# design.net
KiCad netlist of a schematic drawn in Altium Designer
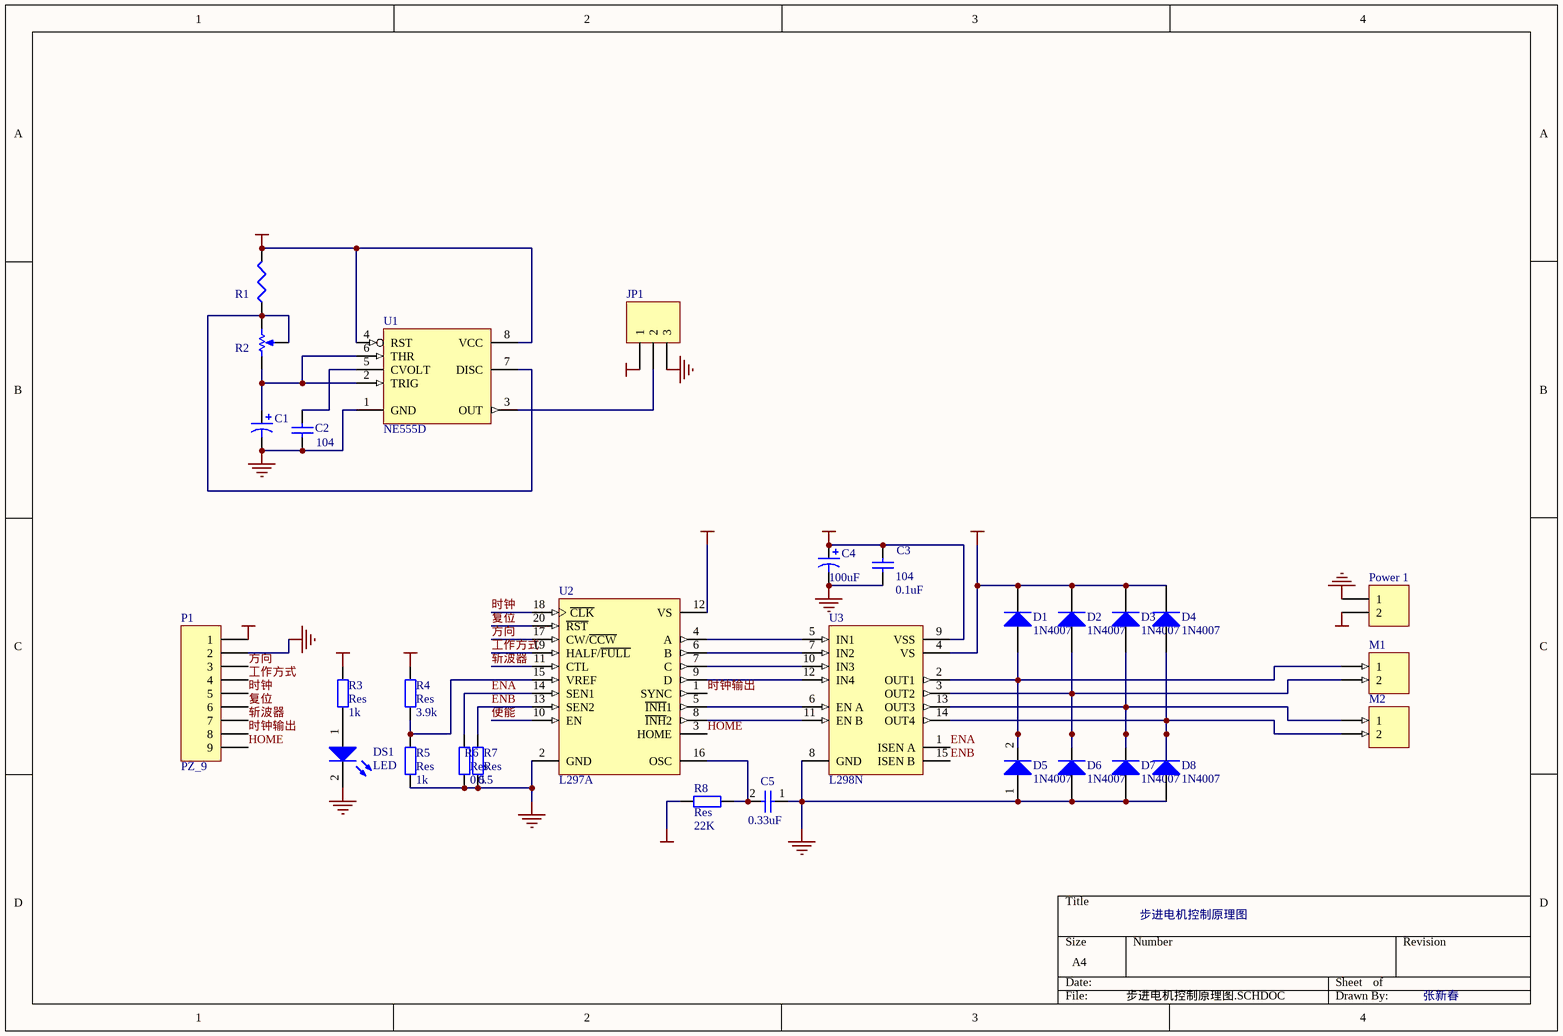
[diagram p0: 步进电机控制原理图.SCHDOC]

(export (version "E")
  (design (tool "Eeschema 10.0.6"))
  (components
    (comp (ref "C1")
      (value "~")
      (footprint "C-DJ-4")
      (description "Polarized Capacitor (Radial)")
      (fields (field (name "PUBLISHER") "Altium Limited"))
      (libsource (lib "Miscellaneous Devices") (part "Cap Pol1"))
    )
    (comp (ref "C2")
      (value "104")
      (footprint "C1608-0603")
      (description "Capacitor (Semiconductor SIM Model)")
      (fields (field (name "PUBLISHER") "Altium Limited"))
      (libsource (lib "Miscellaneous Devices") (part "Cap Semi"))
    )
    (comp (ref "C3")
      (value "104")
      (footprint "CPDR")
      (description "Capacitor")
      (fields (field (name "ALTIUM_VALUE") "0.1uF") (field (name "PUBLISHER") "Altium Limited"))
      (libsource (lib "Miscellaneous Devices") (part "Cap"))
    )
    (comp (ref "C4")
      (value "100uF")
      (footprint "C-DJ-6")
      (description "Polarized Capacitor (Surface Mount)")
      (fields (field (name "PUBLISHER") "Altium Limited"))
      (libsource (lib "Miscellaneous Devices") (part "Cap Pol3"))
    )
    (comp (ref "C5")
      (value "0.33uF")
      (footprint "C-DJ-4")
      (description "Capacitor")
      (fields (field (name "PUBLISHER") "Altium Limited"))
      (libsource (lib "") (part "Cap_1"))
    )
    (comp (ref "D1")
      (value "1N4007")
      (footprint "D-ZL-10")
      (description "1 Amp General Purpose Rectifier")
      (fields (field (name "PUBLISHER") "Altium Limited"))
      (libsource (lib "Miscellaneous Devices") (part "Diode 1N4007"))
    )
    (comp (ref "D2")
      (value "1N4007")
      (footprint "D-ZL-10")
      (description "1 Amp General Purpose Rectifier")
      (fields (field (name "PUBLISHER") "Altium Limited"))
      (libsource (lib "Miscellaneous Devices") (part "Diode 1N4007"))
    )
    (comp (ref "D3")
      (value "1N4007")
      (footprint "D-ZL-10")
      (description "1 Amp General Purpose Rectifier")
      (fields (field (name "PUBLISHER") "Altium Limited"))
      (libsource (lib "Miscellaneous Devices") (part "Diode 1N4007"))
    )
    (comp (ref "D4")
      (value "1N4007")
      (footprint "D-ZL-10")
      (description "1 Amp General Purpose Rectifier")
      (fields (field (name "PUBLISHER") "Altium Limited"))
      (libsource (lib "Miscellaneous Devices") (part "Diode 1N4007"))
    )
    (comp (ref "D5")
      (value "1N4007")
      (footprint "D-ZL-10")
      (description "1 Amp General Purpose Rectifier")
      (fields (field (name "PUBLISHER") "Altium Limited"))
      (libsource (lib "") (part "Diode 1N4007_1"))
    )
    (comp (ref "D6")
      (value "1N4007")
      (footprint "D-ZL-10")
      (description "1 Amp General Purpose Rectifier")
      (fields (field (name "PUBLISHER") "Altium Limited"))
      (libsource (lib "Miscellaneous Devices") (part "Diode 1N4007"))
    )
    (comp (ref "D7")
      (value "1N4007")
      (footprint "D-ZL-10")
      (description "1 Amp General Purpose Rectifier")
      (fields (field (name "PUBLISHER") "Altium Limited"))
      (libsource (lib "Miscellaneous Devices") (part "Diode 1N4007"))
    )
    (comp (ref "D8")
      (value "1N4007")
      (footprint "D-ZL-10")
      (description "1 Amp General Purpose Rectifier")
      (fields (field (name "PUBLISHER") "Altium Limited"))
      (libsource (lib "Miscellaneous Devices") (part "Diode 1N4007"))
    )
    (comp (ref "DS1")
      (value "LED")
      (footprint "CPDR")
      (description "发光二极管")
      (fields (field (name "PUBLISHER") "Altium Limited"))
      (libsource (lib "zxcourhc") (part "LED"))
    )
    (comp (ref "JP1")
      (value "~")
      (footprint "HDR1X3")
      (description "Header, 3-Pin")
      (fields (field (name "PUBLISHER") "Altium Limited"))
      (libsource (lib "Miscellaneous Connectors") (part "Header 3"))
    )
    (comp (ref "M1")
      (value "~")
      (footprint "JK128")
      (description "Header, 2-Pin")
      (fields (field (name "PUBLISHER") "Altium Limited"))
      (libsource (lib "Miscellaneous Connectors") (part "MHDR1X2"))
    )
    (comp (ref "M2")
      (value "~")
      (footprint "JK128")
      (description "Header, 2-Pin")
      (fields (field (name "PUBLISHER") "Altium Limited"))
      (libsource (lib "Miscellaneous Connectors") (part "MHDR1X2"))
    )
    (comp (ref "P1")
      (value "PZ_9")
      (footprint "HDR-9")
      (description "排针——9")
      (fields (field (name "PUBLISHER") "Altium Limited"))
      (libsource (lib "zxcourhc") (part "PZ_9"))
    )
    (comp (ref "Power 1")
      (value "~")
      (footprint "JK128")
      (description "Header, 2-Pin")
      (fields (field (name "PUBLISHER") "Altium Limited"))
      (libsource (lib "Miscellaneous Connectors") (part "MHDR1X2"))
    )
    (comp (ref "R1")
      (value "~")
      (footprint "C1608-0603")
      (description "Resistor")
      (fields (field (name "PUBLISHER") "Altium Limited"))
      (libsource (lib "Miscellaneous Devices") (part "Res3"))
    )
    (comp (ref "R2")
      (value "~")
      (footprint "SIP3-D")
      (description "Potentiometer")
      (fields (field (name "PUBLISHER") "Altium Limited"))
      (libsource (lib "Miscellaneous Devices") (part "RPot"))
    )
    (comp (ref "R3")
      (value "Res")
      (footprint "zxcourhc:CPDR")
      (description "电阻")
      (fields (field (name "ALTIUM_VALUE") "1k") (field (name "PUBLISHER") "Altium Limited"))
      (libsource (lib "zxcourhc") (part "Res"))
    )
    (comp (ref "R4")
      (value "Res")
      (footprint "zxcourhc:CPDR")
      (description "电阻")
      (fields (field (name "ALTIUM_VALUE") "3.9k") (field (name "PUBLISHER") "Altium Limited"))
      (libsource (lib "zxcourhc") (part "Res"))
    )
    (comp (ref "R5")
      (value "Res")
      (footprint "CPDR")
      (description "电阻")
      (fields (field (name "ALTIUM_VALUE") "1k") (field (name "PUBLISHER") "Altium Limited"))
      (libsource (lib "zxcourhc") (part "Res"))
    )
    (comp (ref "R6")
      (value "Res")
      (footprint "ZCDZl")
      (description "电阻")
      (fields (field (name "ALTIUM_VALUE") "0.5") (field (name "PUBLISHER") "Altium Limited"))
      (libsource (lib "zxcourhc") (part "Res"))
    )
    (comp (ref "R7")
      (value "Res")
      (footprint "ZCDZl")
      (description "电阻")
      (fields (field (name "ALTIUM_VALUE") "0.5") (field (name "PUBLISHER") "Altium Limited"))
      (libsource (lib "zxcourhc") (part "Res"))
    )
    (comp (ref "R8")
      (value "Res")
      (footprint "CPDR")
      (description "电阻")
      (fields (field (name "ALTIUM_VALUE") "22K") (field (name "PUBLISHER") "Altium Limited"))
      (libsource (lib "") (part "Res_1"))
    )
    (comp (ref "U1")
      (value "NE555D")
      (footprint "CDFP-8")
      (description "Precision Timer")
      (fields (field (name "MANUFACTURER") "Texas Instruments") (field (name "PUBLISHER") "Altium Limited"))
      (libsource (lib "TI Analog Timer Circuit") (part "NE555D"))
    )
    (comp (ref "U2")
      (value "L297A")
      (footprint "DIP20")
      (description "Stepper Motor Controller")
      (fields (field (name "PUBLISHER") "Altium Limited"))
      (libsource (lib "ST Interface Stepper Motor Controller") (part "L297A"))
    )
    (comp (ref "U3")
      (value "L298N")
      (footprint "zxcourhc:L298N")
      (description "Dual Full Bridge Driver")
      (fields (field (name "PUBLISHER") "Altium Limited"))
      (libsource (lib "ST Interface DC Motor Controller") (part "L298N"))
    )
  )
  (nets
    (net (code "1") (name "+5V") (class "Default")
      (node (ref "C3") (pin "2") (pinfunction "2_2") (pintype "passive"))
      (node (ref "C4") (pin "1") (pinfunction "1_1") (pintype "passive"))
      (node (ref "P1") (pin "1") (pinfunction "1_1") (pintype "passive"))
      (node (ref "R3") (pin "1") (pinfunction "1_1") (pintype "passive"))
      (node (ref "R4") (pin "1") (pinfunction "1_1") (pintype "passive"))
      (node (ref "R8") (pin "2") (pinfunction "2_2") (pintype "passive"))
      (node (ref "U2") (pin "12") (pinfunction "VS_12") (pintype "power_in"))
      (node (ref "U3") (pin "9") (pinfunction "VSS_9") (pintype "power_in"))
    )
    (net (code "2") (name "/ENA") (class "Default")
      (node (ref "R6") (pin "1") (pinfunction "1_1") (pintype "passive"))
      (node (ref "U2") (pin "14") (pinfunction "SEN1_14") (pintype "input"))
      (node (ref "U3") (pin "1") (pinfunction "ISEN_A_1") (pintype "passive"))
    )
    (net (code "3") (name "/ENB") (class "Default")
      (node (ref "R7") (pin "1") (pinfunction "1_1") (pintype "passive"))
      (node (ref "U2") (pin "13") (pinfunction "SEN2_13") (pintype "input"))
      (node (ref "U3") (pin "15") (pinfunction "ISEN_B_15") (pintype "passive"))
    )
    (net (code "4") (name "/HOME") (class "Default")
      (node (ref "P1") (pin "9") (pinfunction "9_9") (pintype "passive"))
      (node (ref "U2") (pin "3") (pinfunction "HOME_3") (pintype "open_collector"))
    )
    (net (code "5") (name "/使能") (class "Default")
      (node (ref "U2") (pin "10") (pinfunction "EN_10") (pintype "input"))
    )
    (net (code "6") (name "/复位") (class "Default")
      (node (ref "P1") (pin "6") (pinfunction "6_6") (pintype "passive"))
      (node (ref "U2") (pin "20") (pinfunction "~{RST}_20") (pintype "input"))
    )
    (net (code "7") (name "/工作方式") (class "Default")
      (node (ref "P1") (pin "4") (pinfunction "4_4") (pintype "passive"))
      (node (ref "U2") (pin "19") (pinfunction "HALF/~{FULL}_19") (pintype "input"))
    )
    (net (code "8") (name "/斩波器") (class "Default")
      (node (ref "P1") (pin "7") (pinfunction "7_7") (pintype "passive"))
      (node (ref "U2") (pin "11") (pinfunction "CTL_11") (pintype "input"))
    )
    (net (code "9") (name "/方向") (class "Default")
      (node (ref "P1") (pin "3") (pinfunction "3_3") (pintype "passive"))
      (node (ref "U2") (pin "17") (pinfunction "CW/~{CCW}_17") (pintype "input"))
    )
    (net (code "10") (name "/时钟") (class "Default")
      (node (ref "P1") (pin "5") (pinfunction "5_5") (pintype "passive"))
      (node (ref "U2") (pin "18") (pinfunction "~{CLK}_18") (pintype "input"))
    )
    (net (code "11") (name "/时钟输出") (class "Default")
      (node (ref "P1") (pin "8") (pinfunction "8_8") (pintype "passive"))
      (node (ref "U2") (pin "1") (pinfunction "SYNC_1") (pintype "output"))
    )
    (net (code "12") (name "GND") (class "Default")
      (node (ref "C1") (pin "2") (pinfunction "2_2") (pintype "passive"))
      (node (ref "C2") (pin "2") (pinfunction "2_2") (pintype "passive"))
      (node (ref "C3") (pin "1") (pinfunction "1_1") (pintype "passive"))
      (node (ref "C4") (pin "2") (pinfunction "2_2") (pintype "passive"))
      (node (ref "DS1") (pin "2") (pinfunction "K_2") (pintype "passive"))
      (node (ref "JP1") (pin "3") (pinfunction "3_3") (pintype "passive"))
      (node (ref "P1") (pin "2") (pinfunction "2_2") (pintype "passive"))
      (node (ref "Power 1") (pin "1") (pinfunction "1_1") (pintype "input"))
      (node (ref "R5") (pin "2") (pinfunction "2_2") (pintype "passive"))
      (node (ref "R6") (pin "2") (pinfunction "2_2") (pintype "passive"))
      (node (ref "R7") (pin "2") (pinfunction "2_2") (pintype "passive"))
      (node (ref "U1") (pin "1") (pinfunction "GND_1") (pintype "power_in"))
      (node (ref "U2") (pin "2") (pinfunction "GND_2") (pintype "power_in"))
    )
    (net (code "13") (name "GND-12") (class "Default")
      (node (ref "C5") (pin "1") (pinfunction "1_1") (pintype "passive"))
      (node (ref "D5") (pin "1") (pinfunction "A_1") (pintype "passive"))
      (node (ref "D6") (pin "1") (pinfunction "A_1") (pintype "passive"))
      (node (ref "D7") (pin "1") (pinfunction "A_1") (pintype "passive"))
      (node (ref "D8") (pin "1") (pinfunction "A_1") (pintype "passive"))
      (node (ref "U3") (pin "8") (pinfunction "GND_8") (pintype "power_in"))
    )
    (net (code "14") (name "Net-(D1-A)") (class "Default")
      (node (ref "D1") (pin "1") (pinfunction "A_1") (pintype "passive"))
      (node (ref "D5") (pin "2") (pinfunction "K_2") (pintype "passive"))
      (node (ref "M1") (pin "1") (pinfunction "1_1") (pintype "input"))
      (node (ref "U3") (pin "2") (pinfunction "OUT1_2") (pintype "output"))
    )
    (net (code "15") (name "Net-(D2-A)") (class "Default")
      (node (ref "D2") (pin "1") (pinfunction "A_1") (pintype "passive"))
      (node (ref "D6") (pin "2") (pinfunction "K_2") (pintype "passive"))
      (node (ref "M1") (pin "2") (pinfunction "2_2") (pintype "input"))
      (node (ref "U3") (pin "3") (pinfunction "OUT2_3") (pintype "output"))
    )
    (net (code "16") (name "Net-(D3-A)") (class "Default")
      (node (ref "D3") (pin "1") (pinfunction "A_1") (pintype "passive"))
      (node (ref "D7") (pin "2") (pinfunction "K_2") (pintype "passive"))
      (node (ref "M2") (pin "1") (pinfunction "1_1") (pintype "input"))
      (node (ref "U3") (pin "13") (pinfunction "OUT3_13") (pintype "output"))
    )
    (net (code "17") (name "Net-(D4-A)") (class "Default")
      (node (ref "D4") (pin "1") (pinfunction "A_1") (pintype "passive"))
      (node (ref "D8") (pin "2") (pinfunction "K_2") (pintype "passive"))
      (node (ref "M2") (pin "2") (pinfunction "2_2") (pintype "input"))
      (node (ref "U3") (pin "14") (pinfunction "OUT4_14") (pintype "output"))
    )
    (net (code "18") (name "Net-(DS1-A)") (class "Default")
      (node (ref "DS1") (pin "1") (pinfunction "A_1") (pintype "passive"))
      (node (ref "R3") (pin "2") (pinfunction "2_2") (pintype "passive"))
    )
    (net (code "19") (name "Net-(R2-BOT)") (class "Default")
      (node (ref "R1") (pin "1") (pinfunction "1_1") (pintype "passive"))
      (node (ref "R2") (pin "2") (pinfunction "BOT_2") (pintype "passive"))
      (node (ref "R2") (pin "3") (pinfunction "TAP_3") (pintype "passive"))
      (node (ref "U1") (pin "7") (pinfunction "DISC_7") (pintype "open_collector"))
    )
    (net (code "20") (name "Net-(R2-TOP)") (class "Default")
      (node (ref "C1") (pin "1") (pinfunction "1_1") (pintype "passive"))
      (node (ref "R2") (pin "1") (pinfunction "TOP_1") (pintype "passive"))
      (node (ref "U1") (pin "2") (pinfunction "TRIG_2") (pintype "input"))
      (node (ref "U1") (pin "6") (pinfunction "THR_6") (pintype "input"))
    )
    (net (code "21") (name "Net-(U1-CVOLT)") (class "Default")
      (node (ref "C2") (pin "1") (pinfunction "1_1") (pintype "passive"))
      (node (ref "U1") (pin "5") (pinfunction "CVOLT_5") (pintype "passive"))
    )
    (net (code "22") (name "Net-(U1-OUT)") (class "Default")
      (node (ref "JP1") (pin "2") (pinfunction "2_2") (pintype "passive"))
      (node (ref "U1") (pin "3") (pinfunction "OUT_3") (pintype "output"))
    )
    (net (code "23") (name "Net-(U2-A)") (class "Default")
      (node (ref "U2") (pin "4") (pinfunction "A_4") (pintype "output"))
      (node (ref "U3") (pin "5") (pinfunction "IN1_5") (pintype "input"))
    )
    (net (code "24") (name "Net-(U2-B)") (class "Default")
      (node (ref "U2") (pin "6") (pinfunction "B_6") (pintype "output"))
      (node (ref "U3") (pin "7") (pinfunction "IN2_7") (pintype "input"))
    )
    (net (code "25") (name "Net-(U2-C)") (class "Default")
      (node (ref "U2") (pin "7") (pinfunction "C_7") (pintype "output"))
      (node (ref "U3") (pin "10") (pinfunction "IN3_10") (pintype "input"))
    )
    (net (code "26") (name "Net-(U2-D)") (class "Default")
      (node (ref "U2") (pin "9") (pinfunction "D_9") (pintype "output"))
      (node (ref "U3") (pin "12") (pinfunction "IN4_12") (pintype "input"))
    )
    (net (code "27") (name "Net-(U2-OSC)") (class "Default")
      (node (ref "C5") (pin "2") (pinfunction "2_2") (pintype "passive"))
      (node (ref "R8") (pin "1") (pinfunction "1_1") (pintype "passive"))
      (node (ref "U2") (pin "16") (pinfunction "OSC_16") (pintype "passive"))
    )
    (net (code "28") (name "Net-(U2-VREF)") (class "Default")
      (node (ref "R4") (pin "2") (pinfunction "2_2") (pintype "passive"))
      (node (ref "R5") (pin "1") (pinfunction "1_1") (pintype "passive"))
      (node (ref "U2") (pin "15") (pinfunction "VREF_15") (pintype "input"))
    )
    (net (code "29") (name "Net-(U2-~{INH}1)") (class "Default")
      (node (ref "U2") (pin "5") (pinfunction "~{INH}1_5") (pintype "output"))
      (node (ref "U3") (pin "6") (pinfunction "EN_A_6") (pintype "input"))
    )
    (net (code "30") (name "Net-(U2-~{INH}2)") (class "Default")
      (node (ref "U2") (pin "8") (pinfunction "~{INH}2_8") (pintype "output"))
      (node (ref "U3") (pin "11") (pinfunction "EN_B_11") (pintype "input"))
    )
    (net (code "31") (name "VCC") (class "Default")
      (node (ref "D1") (pin "2") (pinfunction "K_2") (pintype "passive"))
      (node (ref "D2") (pin "2") (pinfunction "K_2") (pintype "passive"))
      (node (ref "D3") (pin "2") (pinfunction "K_2") (pintype "passive"))
      (node (ref "D4") (pin "2") (pinfunction "K_2") (pintype "passive"))
      (node (ref "JP1") (pin "1") (pinfunction "1_1") (pintype "passive"))
      (node (ref "Power 1") (pin "2") (pinfunction "2_2") (pintype "input"))
      (node (ref "R1") (pin "2") (pinfunction "2_2") (pintype "passive"))
      (node (ref "U1") (pin "4") (pinfunction "RST_4") (pintype "input"))
      (node (ref "U1") (pin "8") (pinfunction "VCC_8") (pintype "power_in"))
      (node (ref "U3") (pin "4") (pinfunction "VS_4") (pintype "power_in"))
    )
  )
)
